# 2_matrix.net
KiCad netlist of a schematic drawn in Altium Designer
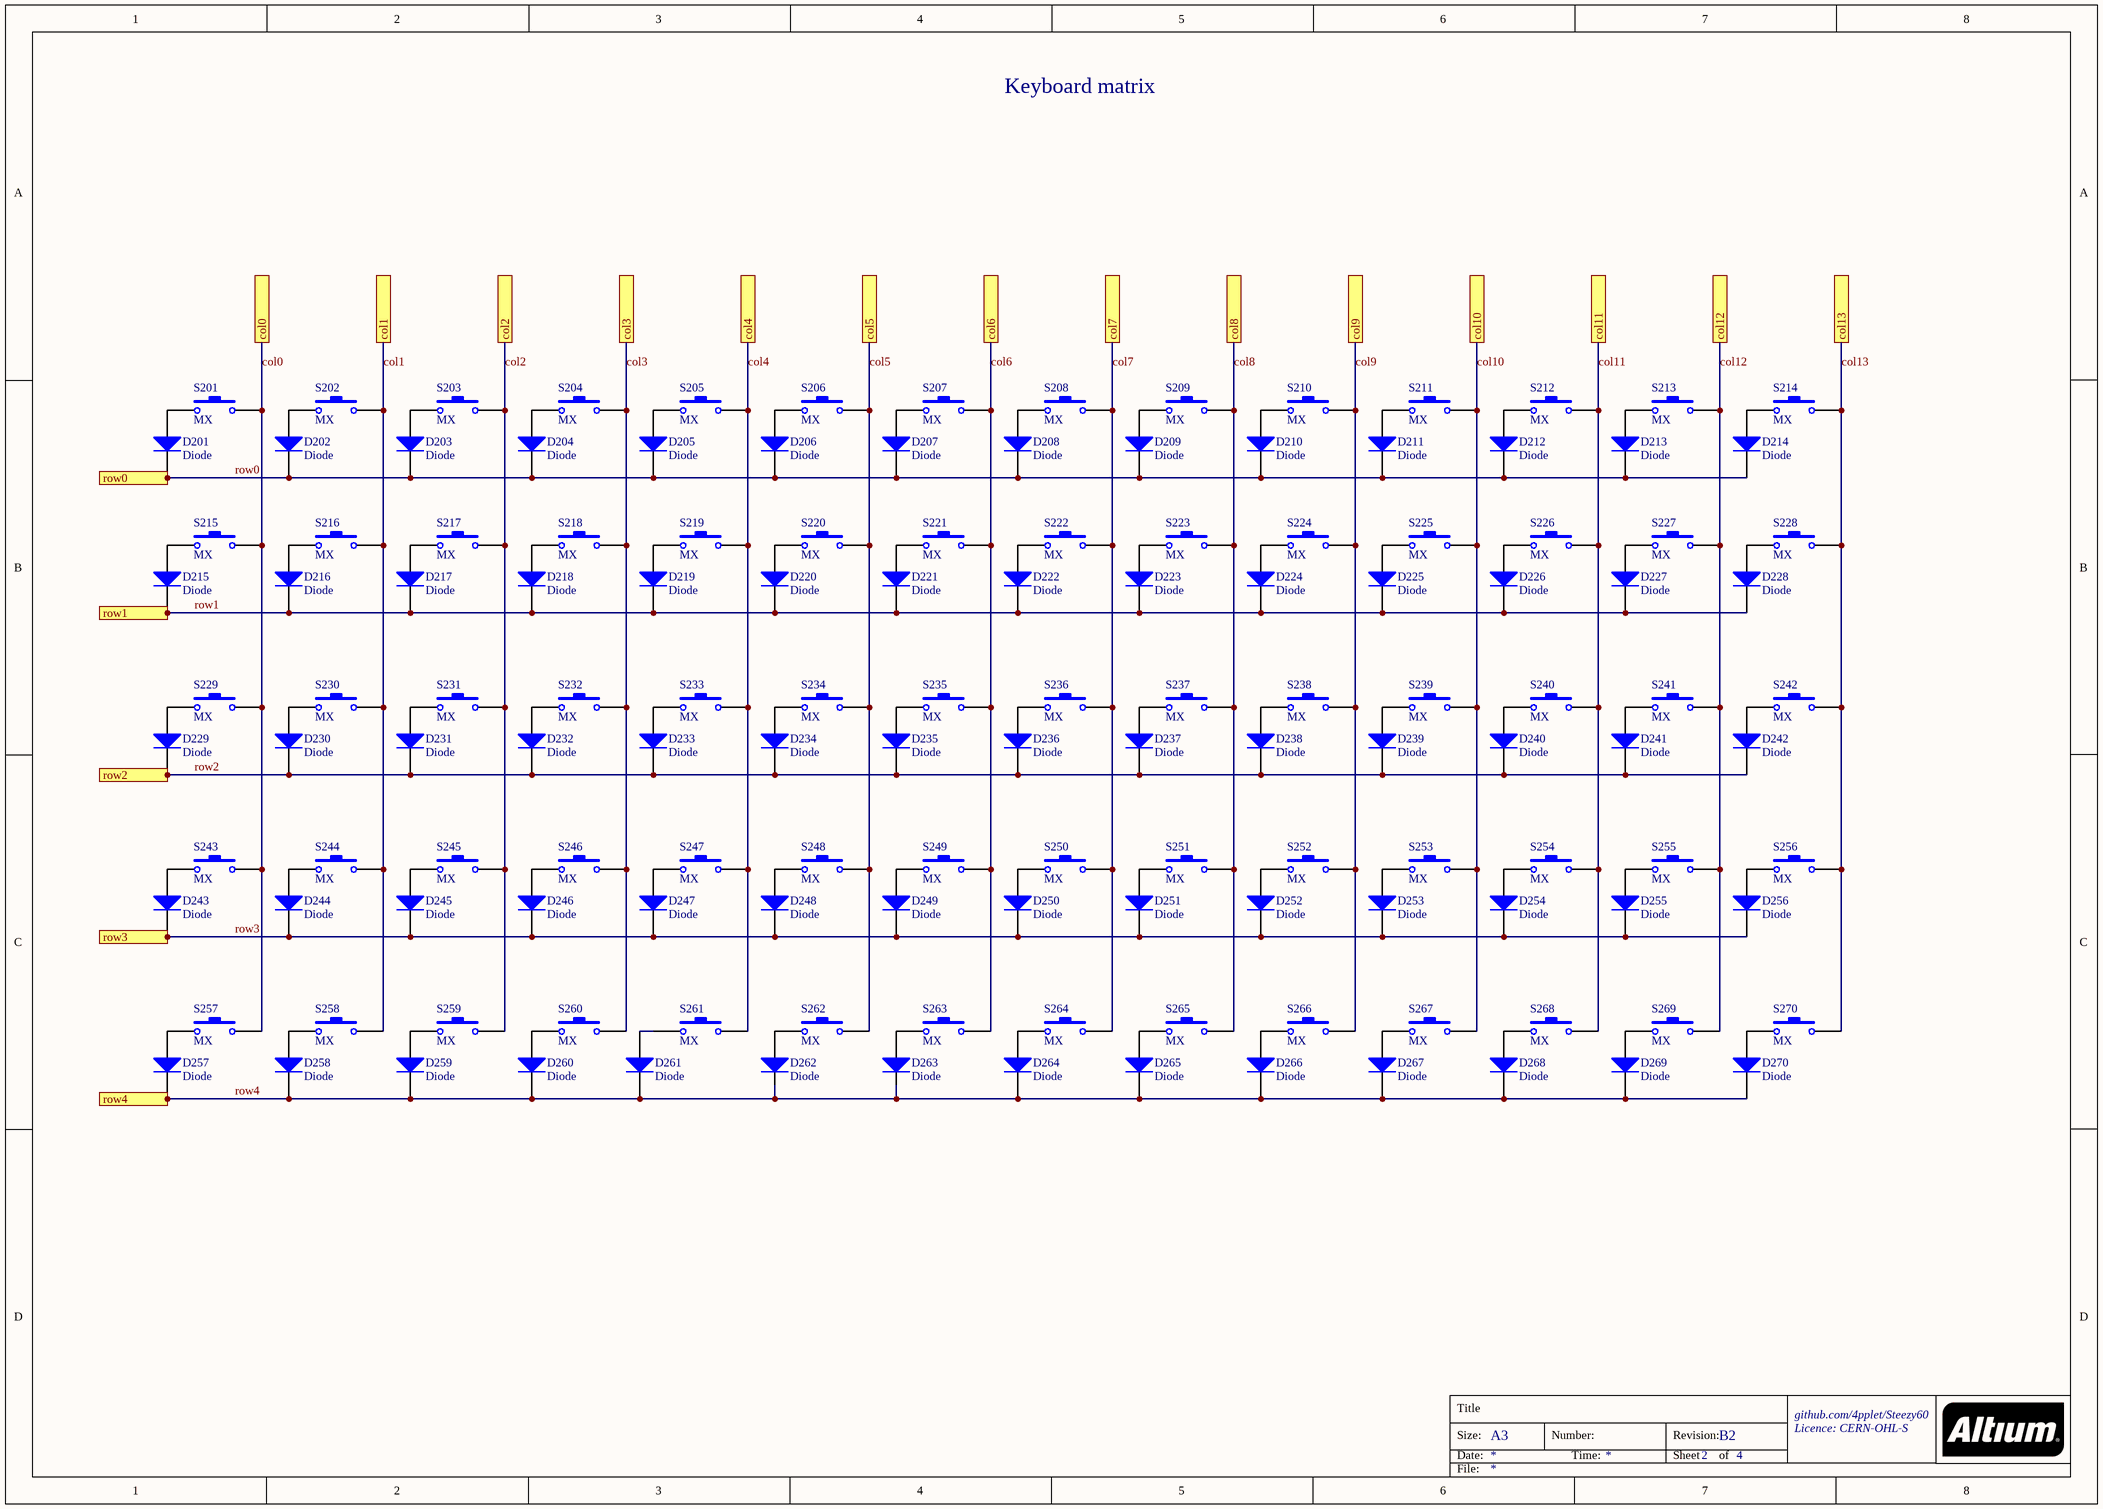
[diagram p0: 2_matrix.SchDoc]

(export (version "E")
  (design (tool "Eeschema 10.0.6"))
  (components
    (comp (ref "D201")
      (value "Diode")
      (footprint "SOD-123")
      (description "Default Diode")
      (fields (field (name "LCSC PART #") "C81598") (field (name "MRF.PART") "1N4148W"))
      (libsource (lib "Miscellaneous Devices") (part "Diode"))
    )
    (comp (ref "D202")
      (value "Diode")
      (footprint "SOD-123")
      (description "Default Diode")
      (fields (field (name "LCSC PART #") "C81598") (field (name "MRF.PART") "1N4148W"))
      (libsource (lib "Miscellaneous Devices") (part "Diode"))
    )
    (comp (ref "D203")
      (value "Diode")
      (footprint "SOD-123")
      (description "Default Diode")
      (fields (field (name "LCSC PART #") "C81598") (field (name "MRF.PART") "1N4148W"))
      (libsource (lib "Miscellaneous Devices") (part "Diode"))
    )
    (comp (ref "D204")
      (value "Diode")
      (footprint "SOD-123")
      (description "Default Diode")
      (fields (field (name "LCSC PART #") "C81598") (field (name "MRF.PART") "1N4148W"))
      (libsource (lib "Miscellaneous Devices") (part "Diode"))
    )
    (comp (ref "D205")
      (value "Diode")
      (footprint "SOD-123")
      (description "Default Diode")
      (fields (field (name "LCSC PART #") "C81598") (field (name "MRF.PART") "1N4148W"))
      (libsource (lib "Miscellaneous Devices") (part "Diode"))
    )
    (comp (ref "D206")
      (value "Diode")
      (footprint "SOD-123")
      (description "Default Diode")
      (fields (field (name "LCSC PART #") "C81598") (field (name "MRF.PART") "1N4148W"))
      (libsource (lib "Miscellaneous Devices") (part "Diode"))
    )
    (comp (ref "D207")
      (value "Diode")
      (footprint "SOD-123")
      (description "Default Diode")
      (fields (field (name "LCSC PART #") "C81598") (field (name "MRF.PART") "1N4148W"))
      (libsource (lib "Miscellaneous Devices") (part "Diode"))
    )
    (comp (ref "D208")
      (value "Diode")
      (footprint "SOD-123")
      (description "Default Diode")
      (fields (field (name "LCSC PART #") "C81598") (field (name "MRF.PART") "1N4148W"))
      (libsource (lib "Miscellaneous Devices") (part "Diode"))
    )
    (comp (ref "D209")
      (value "Diode")
      (footprint "SOD-123")
      (description "Default Diode")
      (fields (field (name "LCSC PART #") "C81598") (field (name "MRF.PART") "1N4148W"))
      (libsource (lib "Miscellaneous Devices") (part "Diode"))
    )
    (comp (ref "D210")
      (value "Diode")
      (footprint "SOD-123")
      (description "Default Diode")
      (fields (field (name "LCSC PART #") "C81598") (field (name "MRF.PART") "1N4148W"))
      (libsource (lib "Miscellaneous Devices") (part "Diode"))
    )
    (comp (ref "D211")
      (value "Diode")
      (footprint "SOD-123")
      (description "Default Diode")
      (fields (field (name "LCSC PART #") "C81598") (field (name "MRF.PART") "1N4148W"))
      (libsource (lib "Miscellaneous Devices") (part "Diode"))
    )
    (comp (ref "D212")
      (value "Diode")
      (footprint "SOD-123")
      (description "Default Diode")
      (fields (field (name "LCSC PART #") "C81598") (field (name "MRF.PART") "1N4148W"))
      (libsource (lib "Miscellaneous Devices") (part "Diode"))
    )
    (comp (ref "D213")
      (value "Diode")
      (footprint "SOD-123")
      (description "Default Diode")
      (fields (field (name "LCSC PART #") "C81598") (field (name "MRF.PART") "1N4148W"))
      (libsource (lib "Miscellaneous Devices") (part "Diode"))
    )
    (comp (ref "D214")
      (value "Diode")
      (footprint "SOD-123")
      (description "Default Diode")
      (fields (field (name "LCSC PART #") "C81598") (field (name "MRF.PART") "1N4148W"))
      (libsource (lib "Miscellaneous Devices") (part "Diode"))
    )
    (comp (ref "D215")
      (value "Diode")
      (footprint "SOD-123")
      (description "Default Diode")
      (fields (field (name "LCSC PART #") "C81598") (field (name "MRF.PART") "1N4148W"))
      (libsource (lib "Miscellaneous Devices") (part "Diode"))
    )
    (comp (ref "D216")
      (value "Diode")
      (footprint "SOD-123")
      (description "Default Diode")
      (fields (field (name "LCSC PART #") "C81598") (field (name "MRF.PART") "1N4148W"))
      (libsource (lib "Miscellaneous Devices") (part "Diode"))
    )
    (comp (ref "D217")
      (value "Diode")
      (footprint "SOD-123")
      (description "Default Diode")
      (fields (field (name "LCSC PART #") "C81598") (field (name "MRF.PART") "1N4148W"))
      (libsource (lib "Miscellaneous Devices") (part "Diode"))
    )
    (comp (ref "D218")
      (value "Diode")
      (footprint "SOD-123")
      (description "Default Diode")
      (fields (field (name "LCSC PART #") "C81598") (field (name "MRF.PART") "1N4148W"))
      (libsource (lib "Miscellaneous Devices") (part "Diode"))
    )
    (comp (ref "D219")
      (value "Diode")
      (footprint "SOD-123")
      (description "Default Diode")
      (fields (field (name "LCSC PART #") "C81598") (field (name "MRF.PART") "1N4148W"))
      (libsource (lib "Miscellaneous Devices") (part "Diode"))
    )
    (comp (ref "D220")
      (value "Diode")
      (footprint "SOD-123")
      (description "Default Diode")
      (fields (field (name "LCSC PART #") "C81598") (field (name "MRF.PART") "1N4148W"))
      (libsource (lib "Miscellaneous Devices") (part "Diode"))
    )
    (comp (ref "D221")
      (value "Diode")
      (footprint "SOD-123")
      (description "Default Diode")
      (fields (field (name "LCSC PART #") "C81598") (field (name "MRF.PART") "1N4148W"))
      (libsource (lib "Miscellaneous Devices") (part "Diode"))
    )
    (comp (ref "D222")
      (value "Diode")
      (footprint "SOD-123")
      (description "Default Diode")
      (fields (field (name "LCSC PART #") "C81598") (field (name "MRF.PART") "1N4148W"))
      (libsource (lib "Miscellaneous Devices") (part "Diode"))
    )
    (comp (ref "D223")
      (value "Diode")
      (footprint "SOD-123")
      (description "Default Diode")
      (fields (field (name "LCSC PART #") "C81598") (field (name "MRF.PART") "1N4148W"))
      (libsource (lib "Miscellaneous Devices") (part "Diode"))
    )
    (comp (ref "D224")
      (value "Diode")
      (footprint "SOD-123")
      (description "Default Diode")
      (fields (field (name "LCSC PART #") "C81598") (field (name "MRF.PART") "1N4148W"))
      (libsource (lib "Miscellaneous Devices") (part "Diode"))
    )
    (comp (ref "D225")
      (value "Diode")
      (footprint "SOD-123")
      (description "Default Diode")
      (fields (field (name "LCSC PART #") "C81598") (field (name "MRF.PART") "1N4148W"))
      (libsource (lib "Miscellaneous Devices") (part "Diode"))
    )
    (comp (ref "D226")
      (value "Diode")
      (footprint "SOD-123")
      (description "Default Diode")
      (fields (field (name "LCSC PART #") "C81598") (field (name "MRF.PART") "1N4148W"))
      (libsource (lib "Miscellaneous Devices") (part "Diode"))
    )
    (comp (ref "D227")
      (value "Diode")
      (footprint "SOD-123")
      (description "Default Diode")
      (fields (field (name "LCSC PART #") "C81598") (field (name "MRF.PART") "1N4148W"))
      (libsource (lib "Miscellaneous Devices") (part "Diode"))
    )
    (comp (ref "D228")
      (value "Diode")
      (footprint "SOD-123")
      (description "Default Diode")
      (fields (field (name "LCSC PART #") "C81598") (field (name "MRF.PART") "1N4148W"))
      (libsource (lib "Miscellaneous Devices") (part "Diode"))
    )
    (comp (ref "D229")
      (value "Diode")
      (footprint "SOD-123")
      (description "Default Diode")
      (fields (field (name "LCSC PART #") "C81598") (field (name "MRF.PART") "1N4148W"))
      (libsource (lib "Miscellaneous Devices") (part "Diode"))
    )
    (comp (ref "D230")
      (value "Diode")
      (footprint "SOD-123")
      (description "Default Diode")
      (fields (field (name "LCSC PART #") "C81598") (field (name "MRF.PART") "1N4148W"))
      (libsource (lib "Miscellaneous Devices") (part "Diode"))
    )
    (comp (ref "D231")
      (value "Diode")
      (footprint "SOD-123")
      (description "Default Diode")
      (fields (field (name "LCSC PART #") "C81598") (field (name "MRF.PART") "1N4148W"))
      (libsource (lib "Miscellaneous Devices") (part "Diode"))
    )
    (comp (ref "D232")
      (value "Diode")
      (footprint "SOD-123")
      (description "Default Diode")
      (fields (field (name "LCSC PART #") "C81598") (field (name "MRF.PART") "1N4148W"))
      (libsource (lib "Miscellaneous Devices") (part "Diode"))
    )
    (comp (ref "D233")
      (value "Diode")
      (footprint "SOD-123")
      (description "Default Diode")
      (fields (field (name "LCSC PART #") "C81598") (field (name "MRF.PART") "1N4148W"))
      (libsource (lib "Miscellaneous Devices") (part "Diode"))
    )
    (comp (ref "D234")
      (value "Diode")
      (footprint "SOD-123")
      (description "Default Diode")
      (fields (field (name "LCSC PART #") "C81598") (field (name "MRF.PART") "1N4148W"))
      (libsource (lib "Miscellaneous Devices") (part "Diode"))
    )
    (comp (ref "D235")
      (value "Diode")
      (footprint "SOD-123")
      (description "Default Diode")
      (fields (field (name "LCSC PART #") "C81598") (field (name "MRF.PART") "1N4148W"))
      (libsource (lib "Miscellaneous Devices") (part "Diode"))
    )
    (comp (ref "D236")
      (value "Diode")
      (footprint "SOD-123")
      (description "Default Diode")
      (fields (field (name "LCSC PART #") "C81598") (field (name "MRF.PART") "1N4148W"))
      (libsource (lib "Miscellaneous Devices") (part "Diode"))
    )
    (comp (ref "D237")
      (value "Diode")
      (footprint "SOD-123")
      (description "Default Diode")
      (fields (field (name "LCSC PART #") "C81598") (field (name "MRF.PART") "1N4148W"))
      (libsource (lib "Miscellaneous Devices") (part "Diode"))
    )
    (comp (ref "D238")
      (value "Diode")
      (footprint "SOD-123")
      (description "Default Diode")
      (fields (field (name "LCSC PART #") "C81598") (field (name "MRF.PART") "1N4148W"))
      (libsource (lib "Miscellaneous Devices") (part "Diode"))
    )
    (comp (ref "D239")
      (value "Diode")
      (footprint "SOD-123")
      (description "Default Diode")
      (fields (field (name "LCSC PART #") "C81598") (field (name "MRF.PART") "1N4148W"))
      (libsource (lib "Miscellaneous Devices") (part "Diode"))
    )
    (comp (ref "D240")
      (value "Diode")
      (footprint "SOD-123")
      (description "Default Diode")
      (fields (field (name "LCSC PART #") "C81598") (field (name "MRF.PART") "1N4148W"))
      (libsource (lib "Miscellaneous Devices") (part "Diode"))
    )
    (comp (ref "D241")
      (value "Diode")
      (footprint "SOD-123")
      (description "Default Diode")
      (fields (field (name "LCSC PART #") "C81598") (field (name "MRF.PART") "1N4148W"))
      (libsource (lib "Miscellaneous Devices") (part "Diode"))
    )
    (comp (ref "D242")
      (value "Diode")
      (footprint "SOD-123")
      (description "Default Diode")
      (fields (field (name "LCSC PART #") "C81598") (field (name "MRF.PART") "1N4148W"))
      (libsource (lib "Miscellaneous Devices") (part "Diode"))
    )
    (comp (ref "D243")
      (value "Diode")
      (footprint "SOD-123")
      (description "Default Diode")
      (fields (field (name "LCSC PART #") "C81598") (field (name "MRF.PART") "1N4148W"))
      (libsource (lib "Miscellaneous Devices") (part "Diode"))
    )
    (comp (ref "D244")
      (value "Diode")
      (footprint "SOD-123")
      (description "Default Diode")
      (fields (field (name "LCSC PART #") "C81598") (field (name "MRF.PART") "1N4148W"))
      (libsource (lib "Miscellaneous Devices") (part "Diode"))
    )
    (comp (ref "D245")
      (value "Diode")
      (footprint "SOD-123")
      (description "Default Diode")
      (fields (field (name "LCSC PART #") "C81598") (field (name "MRF.PART") "1N4148W"))
      (libsource (lib "Miscellaneous Devices") (part "Diode"))
    )
    (comp (ref "D246")
      (value "Diode")
      (footprint "SOD-123")
      (description "Default Diode")
      (fields (field (name "LCSC PART #") "C81598") (field (name "MRF.PART") "1N4148W"))
      (libsource (lib "Miscellaneous Devices") (part "Diode"))
    )
    (comp (ref "D247")
      (value "Diode")
      (footprint "SOD-123")
      (description "Default Diode")
      (fields (field (name "LCSC PART #") "C81598") (field (name "MRF.PART") "1N4148W"))
      (libsource (lib "Miscellaneous Devices") (part "Diode"))
    )
    (comp (ref "D248")
      (value "Diode")
      (footprint "SOD-123")
      (description "Default Diode")
      (fields (field (name "LCSC PART #") "C81598") (field (name "MRF.PART") "1N4148W"))
      (libsource (lib "Miscellaneous Devices") (part "Diode"))
    )
    (comp (ref "D249")
      (value "Diode")
      (footprint "SOD-123")
      (description "Default Diode")
      (fields (field (name "LCSC PART #") "C81598") (field (name "MRF.PART") "1N4148W"))
      (libsource (lib "Miscellaneous Devices") (part "Diode"))
    )
    (comp (ref "D250")
      (value "Diode")
      (footprint "SOD-123")
      (description "Default Diode")
      (fields (field (name "LCSC PART #") "C81598") (field (name "MRF.PART") "1N4148W"))
      (libsource (lib "Miscellaneous Devices") (part "Diode"))
    )
    (comp (ref "D251")
      (value "Diode")
      (footprint "SOD-123")
      (description "Default Diode")
      (fields (field (name "LCSC PART #") "C81598") (field (name "MRF.PART") "1N4148W"))
      (libsource (lib "Miscellaneous Devices") (part "Diode"))
    )
    (comp (ref "D252")
      (value "Diode")
      (footprint "SOD-123")
      (description "Default Diode")
      (fields (field (name "LCSC PART #") "C81598") (field (name "MRF.PART") "1N4148W"))
      (libsource (lib "Miscellaneous Devices") (part "Diode"))
    )
    (comp (ref "D253")
      (value "Diode")
      (footprint "SOD-123")
      (description "Default Diode")
      (fields (field (name "LCSC PART #") "C81598") (field (name "MRF.PART") "1N4148W"))
      (libsource (lib "Miscellaneous Devices") (part "Diode"))
    )
    (comp (ref "D254")
      (value "Diode")
      (footprint "SOD-123")
      (description "Default Diode")
      (fields (field (name "LCSC PART #") "C81598") (field (name "MRF.PART") "1N4148W"))
      (libsource (lib "Miscellaneous Devices") (part "Diode"))
    )
    (comp (ref "D255")
      (value "Diode")
      (footprint "SOD-123")
      (description "Default Diode")
      (fields (field (name "LCSC PART #") "C81598") (field (name "MRF.PART") "1N4148W"))
      (libsource (lib "Miscellaneous Devices") (part "Diode"))
    )
    (comp (ref "D256")
      (value "Diode")
      (footprint "SOD-123")
      (description "Default Diode")
      (fields (field (name "LCSC PART #") "C81598") (field (name "MRF.PART") "1N4148W"))
      (libsource (lib "Miscellaneous Devices") (part "Diode"))
    )
    (comp (ref "D257")
      (value "Diode")
      (footprint "SOD-123")
      (description "Default Diode")
      (fields (field (name "LCSC PART #") "C81598") (field (name "MRF.PART") "1N4148W"))
      (libsource (lib "Miscellaneous Devices") (part "Diode"))
    )
    (comp (ref "D258")
      (value "Diode")
      (footprint "SOD-123")
      (description "Default Diode")
      (fields (field (name "LCSC PART #") "C81598") (field (name "MRF.PART") "1N4148W"))
      (libsource (lib "Miscellaneous Devices") (part "Diode"))
    )
    (comp (ref "D259")
      (value "Diode")
      (footprint "SOD-123")
      (description "Default Diode")
      (fields (field (name "LCSC PART #") "C81598") (field (name "MRF.PART") "1N4148W"))
      (libsource (lib "Miscellaneous Devices") (part "Diode"))
    )
    (comp (ref "D260")
      (value "Diode")
      (footprint "SOD-123")
      (description "Default Diode")
      (fields (field (name "LCSC PART #") "C81598") (field (name "MRF.PART") "1N4148W"))
      (libsource (lib "Miscellaneous Devices") (part "Diode"))
    )
    (comp (ref "D261")
      (value "Diode")
      (footprint "SOD-123")
      (description "Default Diode")
      (fields (field (name "LCSC PART #") "C81598") (field (name "MRF.PART") "1N4148W"))
      (libsource (lib "Miscellaneous Devices") (part "Diode"))
    )
    (comp (ref "D262")
      (value "Diode")
      (footprint "SOD-123")
      (description "Default Diode")
      (fields (field (name "LCSC PART #") "C81598") (field (name "MRF.PART") "1N4148W"))
      (libsource (lib "Miscellaneous Devices") (part "Diode"))
    )
    (comp (ref "D263")
      (value "Diode")
      (footprint "SOD-123")
      (description "Default Diode")
      (fields (field (name "LCSC PART #") "C81598") (field (name "MRF.PART") "1N4148W"))
      (libsource (lib "Miscellaneous Devices") (part "Diode"))
    )
    (comp (ref "D264")
      (value "Diode")
      (footprint "SOD-123")
      (description "Default Diode")
      (fields (field (name "LCSC PART #") "C81598") (field (name "MRF.PART") "1N4148W"))
      (libsource (lib "Miscellaneous Devices") (part "Diode"))
    )
    (comp (ref "D265")
      (value "Diode")
      (footprint "SOD-123")
      (description "Default Diode")
      (fields (field (name "LCSC PART #") "C81598") (field (name "MRF.PART") "1N4148W"))
      (libsource (lib "Miscellaneous Devices") (part "Diode"))
    )
    (comp (ref "D266")
      (value "Diode")
      (footprint "SOD-123")
      (description "Default Diode")
      (fields (field (name "LCSC PART #") "C81598") (field (name "MRF.PART") "1N4148W"))
      (libsource (lib "Miscellaneous Devices") (part "Diode"))
    )
    (comp (ref "D267")
      (value "Diode")
      (footprint "SOD-123")
      (description "Default Diode")
      (fields (field (name "LCSC PART #") "C81598") (field (name "MRF.PART") "1N4148W"))
      (libsource (lib "Miscellaneous Devices") (part "Diode"))
    )
    (comp (ref "D268")
      (value "Diode")
      (footprint "SOD-123")
      (description "Default Diode")
      (fields (field (name "LCSC PART #") "C81598") (field (name "MRF.PART") "1N4148W"))
      (libsource (lib "Miscellaneous Devices") (part "Diode"))
    )
    (comp (ref "D269")
      (value "Diode")
      (footprint "SOD-123")
      (description "Default Diode")
      (fields (field (name "LCSC PART #") "C81598") (field (name "MRF.PART") "1N4148W"))
      (libsource (lib "Miscellaneous Devices") (part "Diode"))
    )
    (comp (ref "D270")
      (value "Diode")
      (footprint "SOD-123")
      (description "Default Diode")
      (fields (field (name "LCSC PART #") "C81598") (field (name "MRF.PART") "1N4148W"))
      (libsource (lib "Miscellaneous Devices") (part "Diode"))
    )
    (comp (ref "S201")
      (value "MX")
      (footprint "SMK-switch - switched polarity")
      (description "Switch")
      (libsource (lib "Miscellaneous Devices") (part "SW-PB"))
    )
    (comp (ref "S202")
      (value "MX")
      (footprint "SMK-switch - switched polarity")
      (description "Switch")
      (libsource (lib "Miscellaneous Devices") (part "SW-PB"))
    )
    (comp (ref "S203")
      (value "MX")
      (footprint "SMK-switch - switched polarity")
      (description "Switch")
      (libsource (lib "Miscellaneous Devices") (part "SW-PB"))
    )
    (comp (ref "S204")
      (value "MX")
      (footprint "SMK-switch - switched polarity")
      (description "Switch")
      (libsource (lib "Miscellaneous Devices") (part "SW-PB"))
    )
    (comp (ref "S205")
      (value "MX")
      (footprint "SMK-switch - switched polarity")
      (description "Switch")
      (libsource (lib "Miscellaneous Devices") (part "SW-PB"))
    )
    (comp (ref "S206")
      (value "MX")
      (footprint "SMK-switch - switched polarity")
      (description "Switch")
      (libsource (lib "Miscellaneous Devices") (part "SW-PB"))
    )
    (comp (ref "S207")
      (value "MX")
      (footprint "SMK-switch - switched polarity")
      (description "Switch")
      (libsource (lib "Miscellaneous Devices") (part "SW-PB"))
    )
    (comp (ref "S208")
      (value "MX")
      (footprint "SMK-switch - switched polarity")
      (description "Switch")
      (libsource (lib "Miscellaneous Devices") (part "SW-PB"))
    )
    (comp (ref "S209")
      (value "MX")
      (footprint "SMK-switch")
      (description "Switch")
      (libsource (lib "Miscellaneous Devices") (part "SW-PB"))
    )
    (comp (ref "S210")
      (value "MX")
      (footprint "SMK-switch")
      (description "Switch")
      (libsource (lib "Miscellaneous Devices") (part "SW-PB"))
    )
    (comp (ref "S211")
      (value "MX")
      (footprint "SMK-switch")
      (description "Switch")
      (libsource (lib "Miscellaneous Devices") (part "SW-PB"))
    )
    (comp (ref "S212")
      (value "MX")
      (footprint "SMK-switch")
      (description "Switch")
      (libsource (lib "Miscellaneous Devices") (part "SW-PB"))
    )
    (comp (ref "S213")
      (value "MX")
      (footprint "SMK-switch")
      (description "Switch")
      (libsource (lib "Miscellaneous Devices") (part "SW-PB"))
    )
    (comp (ref "S214")
      (value "MX")
      (footprint "SMK-switch")
      (description "Switch")
      (libsource (lib "Miscellaneous Devices") (part "SW-PB"))
    )
    (comp (ref "S215")
      (value "MX")
      (footprint "SMK-switch - 1.5U")
      (description "TAB")
      (libsource (lib "Miscellaneous Devices") (part "SW-PB"))
    )
    (comp (ref "S216")
      (value "MX")
      (footprint "SMK-switch")
      (description "Switch")
      (libsource (lib "Miscellaneous Devices") (part "SW-PB"))
    )
    (comp (ref "S217")
      (value "MX")
      (footprint "SMK-switch - switched polarity")
      (description "Switch")
      (libsource (lib "Miscellaneous Devices") (part "SW-PB"))
    )
    (comp (ref "S218")
      (value "MX")
      (footprint "SMK-switch - switched polarity")
      (description "Switch")
      (libsource (lib "Miscellaneous Devices") (part "SW-PB"))
    )
    (comp (ref "S219")
      (value "MX")
      (footprint "SMK-switch - switched polarity")
      (description "Switch")
      (libsource (lib "Miscellaneous Devices") (part "SW-PB"))
    )
    (comp (ref "S220")
      (value "MX")
      (footprint "SMK-switch - switched polarity")
      (description "Switch")
      (libsource (lib "Miscellaneous Devices") (part "SW-PB"))
    )
    (comp (ref "S221")
      (value "MX")
      (footprint "SMK-switch - switched polarity")
      (description "Switch")
      (libsource (lib "Miscellaneous Devices") (part "SW-PB"))
    )
    (comp (ref "S222")
      (value "MX")
      (footprint "SMK-switch - switched polarity")
      (description "Switch")
      (libsource (lib "Miscellaneous Devices") (part "SW-PB"))
    )
    (comp (ref "S223")
      (value "MX")
      (footprint "SMK-switch - switched polarity")
      (description "Switch")
      (libsource (lib "Miscellaneous Devices") (part "SW-PB"))
    )
    (comp (ref "S224")
      (value "MX")
      (footprint "SMK-switch - switched polarity")
      (description "Switch")
      (libsource (lib "Miscellaneous Devices") (part "SW-PB"))
    )
    (comp (ref "S225")
      (value "MX")
      (footprint "SMK-switch")
      (description "Switch")
      (libsource (lib "Miscellaneous Devices") (part "SW-PB"))
    )
    (comp (ref "S226")
      (value "MX")
      (footprint "SMK-switch")
      (description "Switch")
      (libsource (lib "Miscellaneous Devices") (part "SW-PB"))
    )
    (comp (ref "S227")
      (value "MX")
      (footprint "SMK-switch - offset-R")
      (description "Switch")
      (libsource (lib "Miscellaneous Devices") (part "SW-PB"))
    )
    (comp (ref "S228")
      (value "MX")
      (footprint "SMK-switch - 1.5U")
      (description "Switch")
      (libsource (lib "Miscellaneous Devices") (part "SW-PB"))
    )
    (comp (ref "S229")
      (value "MX")
      (footprint "SMK-SWITCH - CAPS - V2")
      (description "Switch")
      (libsource (lib "Miscellaneous Devices") (part "SW-PB"))
    )
    (comp (ref "S230")
      (value "MX")
      (footprint "SMK-switch")
      (description "Switch")
      (libsource (lib "Miscellaneous Devices") (part "SW-PB"))
    )
    (comp (ref "S231")
      (value "MX")
      (footprint "SMK-switch - switched polarity")
      (description "Switch")
      (libsource (lib "Miscellaneous Devices") (part "SW-PB"))
    )
    (comp (ref "S232")
      (value "MX")
      (footprint "SMK-switch - switched polarity")
      (description "Switch")
      (libsource (lib "Miscellaneous Devices") (part "SW-PB"))
    )
    (comp (ref "S233")
      (value "MX")
      (footprint "SMK-switch")
      (description "Switch")
      (libsource (lib "Miscellaneous Devices") (part "SW-PB"))
    )
    (comp (ref "S234")
      (value "MX")
      (footprint "SMK-switch - switched polarity")
      (description "Switch")
      (libsource (lib "Miscellaneous Devices") (part "SW-PB"))
    )
    (comp (ref "S235")
      (value "MX")
      (footprint "SMK-switch - switched polarity")
      (description "Switch")
      (libsource (lib "Miscellaneous Devices") (part "SW-PB"))
    )
    (comp (ref "S236")
      (value "MX")
      (footprint "SMK-switch - switched polarity")
      (description "Switch")
      (libsource (lib "Miscellaneous Devices") (part "SW-PB"))
    )
    (comp (ref "S237")
      (value "MX")
      (footprint "SMK-switch - switched polarity")
      (description "Switch")
      (libsource (lib "Miscellaneous Devices") (part "SW-PB"))
    )
    (comp (ref "S238")
      (value "MX")
      (footprint "SMK-switch - switched polarity")
      (description "Switch")
      (libsource (lib "Miscellaneous Devices") (part "SW-PB"))
    )
    (comp (ref "S239")
      (value "MX")
      (footprint "SMK-switch")
      (description "Switch")
      (libsource (lib "Miscellaneous Devices") (part "SW-PB"))
    )
    (comp (ref "S240")
      (value "MX")
      (footprint "SMK-switch")
      (description "Switch")
      (libsource (lib "Miscellaneous Devices") (part "SW-PB"))
    )
    (comp (ref "S241")
      (value "MX")
      (footprint "SMK-switch")
      (description "Switch")
      (libsource (lib "Miscellaneous Devices") (part "SW-PB"))
    )
    (comp (ref "S242")
      (value "MX")
      (footprint "SMK-switch - Enter - rotated stab")
      (description "Switch")
      (libsource (lib "Miscellaneous Devices") (part "SW-PB"))
    )
    (comp (ref "S243")
      (value "MX")
      (footprint "SMK-switch - Left shift")
      (description "Switch")
      (libsource (lib "Miscellaneous Devices") (part "SW-PB"))
    )
    (comp (ref "S244")
      (value "MX")
      (footprint "SMK-switch - smalleroffset-R")
      (description "Switch")
      (libsource (lib "Miscellaneous Devices") (part "SW-PB"))
    )
    (comp (ref "S245")
      (value "MX")
      (footprint "SMK-switch - offset")
      (description "Switch")
      (libsource (lib "Miscellaneous Devices") (part "SW-PB"))
    )
    (comp (ref "S246")
      (value "MX")
      (footprint "SMK-switch - offset")
      (description "Switch")
      (libsource (lib "Miscellaneous Devices") (part "SW-PB"))
    )
    (comp (ref "S247")
      (value "MX")
      (footprint "SMK-switch - offset")
      (description "Switch")
      (libsource (lib "Miscellaneous Devices") (part "SW-PB"))
    )
    (comp (ref "S248")
      (value "MX")
      (footprint "SMK-switch - offset")
      (description "Switch")
      (libsource (lib "Miscellaneous Devices") (part "SW-PB"))
    )
    (comp (ref "S249")
      (value "MX")
      (footprint "SMK-switch - offset")
      (description "Switch")
      (libsource (lib "Miscellaneous Devices") (part "SW-PB"))
    )
    (comp (ref "S250")
      (value "MX")
      (footprint "SMK-switch - offset")
      (description "Switch")
      (libsource (lib "Miscellaneous Devices") (part "SW-PB"))
    )
    (comp (ref "S251")
      (value "MX")
      (footprint "SMK-switch - offset")
      (description "Switch")
      (libsource (lib "Miscellaneous Devices") (part "SW-PB"))
    )
    (comp (ref "S252")
      (value "MX")
      (footprint "SMK-switch - offset")
      (description "Switch")
      (libsource (lib "Miscellaneous Devices") (part "SW-PB"))
    )
    (comp (ref "S253")
      (value "MX")
      (footprint "SMK-switch - offset")
      (description "Switch")
      (libsource (lib "Miscellaneous Devices") (part "SW-PB"))
    )
    (comp (ref "S254")
      (value "MX")
      (footprint "SMK-switch - offset")
      (description "Switch")
      (libsource (lib "Miscellaneous Devices") (part "SW-PB"))
    )
    (comp (ref "S255")
      (value "MX")
      (footprint "SMK-switch - CRAZY SHIFT")
      (description "Switch")
      (libsource (lib "Miscellaneous Devices") (part "SW-PB"))
    )
    (comp (ref "S256")
      (value "MX")
      (footprint "SMK-switch - right shift")
      (description "Switch")
      (libsource (lib "Miscellaneous Devices") (part "SW-PB"))
    )
    (comp (ref "S257")
      (value "MX")
      (footprint "SMK-switch - L_CTRL")
      (description "Switch")
      (libsource (lib "Miscellaneous Devices") (part "SW-PB"))
    )
    (comp (ref "S258")
      (value "MX")
      (footprint "SMK-switch - L_WIN")
      (description "Switch")
      (libsource (lib "Miscellaneous Devices") (part "SW-PB"))
    )
    (comp (ref "S259")
      (value "MX")
      (footprint "SMK-switch")
      (description "Switch")
      (libsource (lib "Miscellaneous Devices") (part "SW-PB"))
    )
    (comp (ref "S260")
      (value "MX")
      (footprint "SMK-switch - L_alt")
      (description "Switch")
      (libsource (lib "Miscellaneous Devices") (part "SW-PB"))
    )
    (comp (ref "S261")
      (value "MX")
      (footprint "SMK-switch - L split space")
      (description "Switch")
      (libsource (lib "Miscellaneous Devices") (part "SW-PB"))
    )
    (comp (ref "S262")
      (value "MX")
      (footprint "SMK-switch - Space")
      (description "Switch")
      (libsource (lib "Miscellaneous Devices") (part "SW-PB"))
    )
    (comp (ref "S263")
      (value "MX")
      (footprint "SMK-switch - R split space")
      (description "Switch")
      (libsource (lib "Miscellaneous Devices") (part "SW-PB"))
    )
    (comp (ref "S264")
      (value "MX")
      (footprint "SMK-switch - R PN")
      (description "Switch")
      (libsource (lib "Miscellaneous Devices") (part "SW-PB"))
    )
    (comp (ref "S265")
      (value "MX")
      (footprint "SMK-switch - R_alt")
      (description "Switch")
      (libsource (lib "Miscellaneous Devices") (part "SW-PB"))
    )
    (comp (ref "S266")
      (value "MX")
      (footprint "SMK-switch")
      (description "Switch")
      (libsource (lib "Miscellaneous Devices") (part "SW-PB"))
    )
    (comp (ref "S267")
      (value "MX")
      (footprint "SMK-switch - R_WIN")
      (description "Switch")
      (libsource (lib "Miscellaneous Devices") (part "SW-PB"))
    )
    (comp (ref "S268")
      (value "MX")
      (footprint "SMK-switch - R_CTRL")
      (description "Switch")
      (libsource (lib "Miscellaneous Devices") (part "SW-PB"))
    )
    (comp (ref "S269")
      (value "MX")
      (footprint "SMK-switch - fn and shift")
      (description "Switch")
      (libsource (lib "Miscellaneous Devices") (part "SW-PB"))
    )
    (comp (ref "S270")
      (value "MX")
      (footprint "SMK-switch - backspace")
      (description "Switch")
      (libsource (lib "Miscellaneous Devices") (part "SW-PB"))
    )
  )
  (nets
    (net (code "1") (name "/col0") (class "Default")
      (node (ref "S201") (pin "2") (pinfunction "2_2") (pintype "passive"))
      (node (ref "S215") (pin "1") (pinfunction "1_1") (pintype "passive"))
      (node (ref "S229") (pin "2") (pinfunction "2_2") (pintype "passive"))
      (node (ref "S243") (pin "2") (pinfunction "2_2") (pintype "passive"))
      (node (ref "S257") (pin "2") (pinfunction "2_2") (pintype "passive"))
    )
    (net (code "2") (name "/col1") (class "Default")
      (node (ref "S202") (pin "2") (pinfunction "2_2") (pintype "passive"))
      (node (ref "S216") (pin "2") (pinfunction "2_2") (pintype "passive"))
      (node (ref "S230") (pin "2") (pinfunction "2_2") (pintype "passive"))
      (node (ref "S244") (pin "2") (pinfunction "2_2") (pintype "passive"))
      (node (ref "S258") (pin "2") (pinfunction "2_2") (pintype "passive"))
    )
    (net (code "3") (name "/col2") (class "Default")
      (node (ref "S203") (pin "2") (pinfunction "2_2") (pintype "passive"))
      (node (ref "S217") (pin "2") (pinfunction "2_2") (pintype "passive"))
      (node (ref "S231") (pin "2") (pinfunction "2_2") (pintype "passive"))
      (node (ref "S245") (pin "2") (pinfunction "2_2") (pintype "passive"))
      (node (ref "S259") (pin "2") (pinfunction "2_2") (pintype "passive"))
    )
    (net (code "4") (name "/col3") (class "Default")
      (node (ref "S204") (pin "2") (pinfunction "2_2") (pintype "passive"))
      (node (ref "S218") (pin "2") (pinfunction "2_2") (pintype "passive"))
      (node (ref "S232") (pin "2") (pinfunction "2_2") (pintype "passive"))
      (node (ref "S246") (pin "2") (pinfunction "2_2") (pintype "passive"))
      (node (ref "S260") (pin "2") (pinfunction "2_2") (pintype "passive"))
    )
    (net (code "5") (name "/col4") (class "Default")
      (node (ref "S205") (pin "2") (pinfunction "2_2") (pintype "passive"))
      (node (ref "S219") (pin "2") (pinfunction "2_2") (pintype "passive"))
      (node (ref "S233") (pin "2") (pinfunction "2_2") (pintype "passive"))
      (node (ref "S247") (pin "2") (pinfunction "2_2") (pintype "passive"))
      (node (ref "S261") (pin "2") (pinfunction "2_2") (pintype "passive"))
    )
    (net (code "6") (name "/col5") (class "Default")
      (node (ref "S206") (pin "2") (pinfunction "2_2") (pintype "passive"))
      (node (ref "S220") (pin "2") (pinfunction "2_2") (pintype "passive"))
      (node (ref "S234") (pin "2") (pinfunction "2_2") (pintype "passive"))
      (node (ref "S248") (pin "2") (pinfunction "2_2") (pintype "passive"))
      (node (ref "S262") (pin "2") (pinfunction "2_2") (pintype "passive"))
    )
    (net (code "7") (name "/col6") (class "Default")
      (node (ref "S207") (pin "2") (pinfunction "2_2") (pintype "passive"))
      (node (ref "S221") (pin "2") (pinfunction "2_2") (pintype "passive"))
      (node (ref "S235") (pin "2") (pinfunction "2_2") (pintype "passive"))
      (node (ref "S249") (pin "2") (pinfunction "2_2") (pintype "passive"))
      (node (ref "S263") (pin "2") (pinfunction "2_2") (pintype "passive"))
    )
    (net (code "8") (name "/col7") (class "Default")
      (node (ref "S208") (pin "2") (pinfunction "2_2") (pintype "passive"))
      (node (ref "S222") (pin "2") (pinfunction "2_2") (pintype "passive"))
      (node (ref "S236") (pin "2") (pinfunction "2_2") (pintype "passive"))
      (node (ref "S250") (pin "2") (pinfunction "2_2") (pintype "passive"))
      (node (ref "S264") (pin "2") (pinfunction "2_2") (pintype "passive"))
    )
    (net (code "9") (name "/col8") (class "Default")
      (node (ref "S209") (pin "2") (pinfunction "2_2") (pintype "passive"))
      (node (ref "S223") (pin "2") (pinfunction "2_2") (pintype "passive"))
      (node (ref "S237") (pin "2") (pinfunction "2_2") (pintype "passive"))
      (node (ref "S251") (pin "2") (pinfunction "2_2") (pintype "passive"))
      (node (ref "S265") (pin "2") (pinfunction "2_2") (pintype "passive"))
    )
    (net (code "10") (name "/col9") (class "Default")
      (node (ref "S210") (pin "2") (pinfunction "2_2") (pintype "passive"))
      (node (ref "S224") (pin "2") (pinfunction "2_2") (pintype "passive"))
      (node (ref "S238") (pin "2") (pinfunction "2_2") (pintype "passive"))
      (node (ref "S252") (pin "2") (pinfunction "2_2") (pintype "passive"))
      (node (ref "S266") (pin "2") (pinfunction "2_2") (pintype "passive"))
    )
    (net (code "11") (name "/col10") (class "Default")
      (node (ref "S211") (pin "2") (pinfunction "2_2") (pintype "passive"))
      (node (ref "S225") (pin "2") (pinfunction "2_2") (pintype "passive"))
      (node (ref "S239") (pin "2") (pinfunction "2_2") (pintype "passive"))
      (node (ref "S253") (pin "2") (pinfunction "2_2") (pintype "passive"))
      (node (ref "S267") (pin "2") (pinfunction "2_2") (pintype "passive"))
    )
    (net (code "12") (name "/col11") (class "Default")
      (node (ref "S212") (pin "2") (pinfunction "2_2") (pintype "passive"))
      (node (ref "S226") (pin "2") (pinfunction "2_2") (pintype "passive"))
      (node (ref "S240") (pin "2") (pinfunction "2_2") (pintype "passive"))
      (node (ref "S254") (pin "2") (pinfunction "2_2") (pintype "passive"))
      (node (ref "S268") (pin "2") (pinfunction "2_2") (pintype "passive"))
    )
    (net (code "13") (name "/col12") (class "Default")
      (node (ref "S213") (pin "2") (pinfunction "2_2") (pintype "passive"))
      (node (ref "S227") (pin "2") (pinfunction "2_2") (pintype "passive"))
      (node (ref "S241") (pin "2") (pinfunction "2_2") (pintype "passive"))
      (node (ref "S255") (pin "2") (pinfunction "2_2") (pintype "passive"))
      (node (ref "S269") (pin "2") (pinfunction "2_2") (pintype "passive"))
    )
    (net (code "14") (name "/col13") (class "Default")
      (node (ref "S214") (pin "2") (pinfunction "2_2") (pintype "passive"))
      (node (ref "S228") (pin "2") (pinfunction "2_2") (pintype "passive"))
      (node (ref "S242") (pin "2") (pinfunction "2_2") (pintype "passive"))
      (node (ref "S256") (pin "2") (pinfunction "2_2") (pintype "passive"))
      (node (ref "S270") (pin "2") (pinfunction "2_2") (pintype "passive"))
    )
    (net (code "15") (name "/row0") (class "Default")
      (node (ref "D201") (pin "2") (pinfunction "K_2") (pintype "passive"))
      (node (ref "D202") (pin "2") (pinfunction "K_2") (pintype "passive"))
      (node (ref "D203") (pin "2") (pinfunction "K_2") (pintype "passive"))
      (node (ref "D204") (pin "2") (pinfunction "K_2") (pintype "passive"))
      (node (ref "D205") (pin "2") (pinfunction "K_2") (pintype "passive"))
      (node (ref "D206") (pin "2") (pinfunction "K_2") (pintype "passive"))
      (node (ref "D207") (pin "2") (pinfunction "K_2") (pintype "passive"))
      (node (ref "D208") (pin "2") (pinfunction "K_2") (pintype "passive"))
      (node (ref "D209") (pin "2") (pinfunction "K_2") (pintype "passive"))
      (node (ref "D210") (pin "2") (pinfunction "K_2") (pintype "passive"))
      (node (ref "D211") (pin "2") (pinfunction "K_2") (pintype "passive"))
      (node (ref "D212") (pin "2") (pinfunction "K_2") (pintype "passive"))
      (node (ref "D213") (pin "2") (pinfunction "K_2") (pintype "passive"))
      (node (ref "D214") (pin "2") (pinfunction "K_2") (pintype "passive"))
    )
    (net (code "16") (name "/row1") (class "Default")
      (node (ref "D215") (pin "2") (pinfunction "K_2") (pintype "passive"))
      (node (ref "D216") (pin "2") (pinfunction "K_2") (pintype "passive"))
      (node (ref "D217") (pin "2") (pinfunction "K_2") (pintype "passive"))
      (node (ref "D218") (pin "2") (pinfunction "K_2") (pintype "passive"))
      (node (ref "D219") (pin "2") (pinfunction "K_2") (pintype "passive"))
      (node (ref "D220") (pin "2") (pinfunction "K_2") (pintype "passive"))
      (node (ref "D221") (pin "2") (pinfunction "K_2") (pintype "passive"))
      (node (ref "D222") (pin "2") (pinfunction "K_2") (pintype "passive"))
      (node (ref "D223") (pin "2") (pinfunction "K_2") (pintype "passive"))
      (node (ref "D224") (pin "2") (pinfunction "K_2") (pintype "passive"))
      (node (ref "D225") (pin "2") (pinfunction "K_2") (pintype "passive"))
      (node (ref "D226") (pin "2") (pinfunction "K_2") (pintype "passive"))
      (node (ref "D227") (pin "2") (pinfunction "K_2") (pintype "passive"))
      (node (ref "D228") (pin "2") (pinfunction "K_2") (pintype "passive"))
    )
    (net (code "17") (name "/row2") (class "Default")
      (node (ref "D229") (pin "2") (pinfunction "K_2") (pintype "passive"))
      (node (ref "D230") (pin "2") (pinfunction "K_2") (pintype "passive"))
      (node (ref "D231") (pin "2") (pinfunction "K_2") (pintype "passive"))
      (node (ref "D232") (pin "2") (pinfunction "K_2") (pintype "passive"))
      (node (ref "D233") (pin "2") (pinfunction "K_2") (pintype "passive"))
      (node (ref "D234") (pin "2") (pinfunction "K_2") (pintype "passive"))
      (node (ref "D235") (pin "2") (pinfunction "K_2") (pintype "passive"))
      (node (ref "D236") (pin "2") (pinfunction "K_2") (pintype "passive"))
      (node (ref "D237") (pin "2") (pinfunction "K_2") (pintype "passive"))
      (node (ref "D238") (pin "2") (pinfunction "K_2") (pintype "passive"))
      (node (ref "D239") (pin "2") (pinfunction "K_2") (pintype "passive"))
      (node (ref "D240") (pin "2") (pinfunction "K_2") (pintype "passive"))
      (node (ref "D241") (pin "2") (pinfunction "K_2") (pintype "passive"))
      (node (ref "D242") (pin "2") (pinfunction "K_2") (pintype "passive"))
    )
    (net (code "18") (name "/row3") (class "Default")
      (node (ref "D243") (pin "2") (pinfunction "K_2") (pintype "passive"))
      (node (ref "D244") (pin "2") (pinfunction "K_2") (pintype "passive"))
      (node (ref "D245") (pin "2") (pinfunction "K_2") (pintype "passive"))
      (node (ref "D246") (pin "2") (pinfunction "K_2") (pintype "passive"))
      (node (ref "D247") (pin "2") (pinfunction "K_2") (pintype "passive"))
      (node (ref "D248") (pin "2") (pinfunction "K_2") (pintype "passive"))
      (node (ref "D249") (pin "2") (pinfunction "K_2") (pintype "passive"))
      (node (ref "D250") (pin "2") (pinfunction "K_2") (pintype "passive"))
      (node (ref "D251") (pin "2") (pinfunction "K_2") (pintype "passive"))
      (node (ref "D252") (pin "2") (pinfunction "K_2") (pintype "passive"))
      (node (ref "D253") (pin "2") (pinfunction "K_2") (pintype "passive"))
      (node (ref "D254") (pin "2") (pinfunction "K_2") (pintype "passive"))
      (node (ref "D255") (pin "2") (pinfunction "K_2") (pintype "passive"))
      (node (ref "D256") (pin "2") (pinfunction "K_2") (pintype "passive"))
    )
    (net (code "19") (name "/row4") (class "Default")
      (node (ref "D257") (pin "2") (pinfunction "K_2") (pintype "passive"))
      (node (ref "D258") (pin "2") (pinfunction "K_2") (pintype "passive"))
      (node (ref "D259") (pin "2") (pinfunction "K_2") (pintype "passive"))
      (node (ref "D260") (pin "2") (pinfunction "K_2") (pintype "passive"))
      (node (ref "D261") (pin "2") (pinfunction "K_2") (pintype "passive"))
      (node (ref "D262") (pin "2") (pinfunction "K_2") (pintype "passive"))
      (node (ref "D263") (pin "2") (pinfunction "K_2") (pintype "passive"))
      (node (ref "D264") (pin "2") (pinfunction "K_2") (pintype "passive"))
      (node (ref "D265") (pin "2") (pinfunction "K_2") (pintype "passive"))
      (node (ref "D266") (pin "2") (pinfunction "K_2") (pintype "passive"))
      (node (ref "D267") (pin "2") (pinfunction "K_2") (pintype "passive"))
      (node (ref "D268") (pin "2") (pinfunction "K_2") (pintype "passive"))
      (node (ref "D269") (pin "2") (pinfunction "K_2") (pintype "passive"))
      (node (ref "D270") (pin "2") (pinfunction "K_2") (pintype "passive"))
    )
    (net (code "20") (name "Net-(D201-A)") (class "Default")
      (node (ref "D201") (pin "1") (pinfunction "A_1") (pintype "passive"))
      (node (ref "S201") (pin "1") (pinfunction "1_1") (pintype "passive"))
    )
    (net (code "21") (name "Net-(D202-A)") (class "Default")
      (node (ref "D202") (pin "1") (pinfunction "A_1") (pintype "passive"))
      (node (ref "S202") (pin "1") (pinfunction "1_1") (pintype "passive"))
    )
    (net (code "22") (name "Net-(D203-A)") (class "Default")
      (node (ref "D203") (pin "1") (pinfunction "A_1") (pintype "passive"))
      (node (ref "S203") (pin "1") (pinfunction "1_1") (pintype "passive"))
    )
    (net (code "23") (name "Net-(D204-A)") (class "Default")
      (node (ref "D204") (pin "1") (pinfunction "A_1") (pintype "passive"))
      (node (ref "S204") (pin "1") (pinfunction "1_1") (pintype "passive"))
    )
    (net (code "24") (name "Net-(D205-A)") (class "Default")
      (node (ref "D205") (pin "1") (pinfunction "A_1") (pintype "passive"))
      (node (ref "S205") (pin "1") (pinfunction "1_1") (pintype "passive"))
    )
    (net (code "25") (name "Net-(D206-A)") (class "Default")
      (node (ref "D206") (pin "1") (pinfunction "A_1") (pintype "passive"))
      (node (ref "S206") (pin "1") (pinfunction "1_1") (pintype "passive"))
    )
    (net (code "26") (name "Net-(D207-A)") (class "Default")
      (node (ref "D207") (pin "1") (pinfunction "A_1") (pintype "passive"))
      (node (ref "S207") (pin "1") (pinfunction "1_1") (pintype "passive"))
    )
    (net (code "27") (name "Net-(D208-A)") (class "Default")
      (node (ref "D208") (pin "1") (pinfunction "A_1") (pintype "passive"))
      (node (ref "S208") (pin "1") (pinfunction "1_1") (pintype "passive"))
    )
    (net (code "28") (name "Net-(D209-A)") (class "Default")
      (node (ref "D209") (pin "1") (pinfunction "A_1") (pintype "passive"))
      (node (ref "S209") (pin "1") (pinfunction "1_1") (pintype "passive"))
    )
    (net (code "29") (name "Net-(D210-A)") (class "Default")
      (node (ref "D210") (pin "1") (pinfunction "A_1") (pintype "passive"))
      (node (ref "S210") (pin "1") (pinfunction "1_1") (pintype "passive"))
    )
    (net (code "30") (name "Net-(D211-A)") (class "Default")
      (node (ref "D211") (pin "1") (pinfunction "A_1") (pintype "passive"))
      (node (ref "S211") (pin "1") (pinfunction "1_1") (pintype "passive"))
    )
    (net (code "31") (name "Net-(D212-A)") (class "Default")
      (node (ref "D212") (pin "1") (pinfunction "A_1") (pintype "passive"))
      (node (ref "S212") (pin "1") (pinfunction "1_1") (pintype "passive"))
    )
    (net (code "32") (name "Net-(D213-A)") (class "Default")
      (node (ref "D213") (pin "1") (pinfunction "A_1") (pintype "passive"))
      (node (ref "S213") (pin "1") (pinfunction "1_1") (pintype "passive"))
    )
    (net (code "33") (name "Net-(D214-A)") (class "Default")
      (node (ref "D214") (pin "1") (pinfunction "A_1") (pintype "passive"))
      (node (ref "S214") (pin "1") (pinfunction "1_1") (pintype "passive"))
    )
    (net (code "34") (name "Net-(D215-A)") (class "Default")
      (node (ref "D215") (pin "1") (pinfunction "A_1") (pintype "passive"))
      (node (ref "S215") (pin "2") (pinfunction "2_2") (pintype "passive"))
    )
    (net (code "35") (name "Net-(D216-A)") (class "Default")
      (node (ref "D216") (pin "1") (pinfunction "A_1") (pintype "passive"))
      (node (ref "S216") (pin "1") (pinfunction "1_1") (pintype "passive"))
    )
    (net (code "36") (name "Net-(D217-A)") (class "Default")
      (node (ref "D217") (pin "1") (pinfunction "A_1") (pintype "passive"))
      (node (ref "S217") (pin "1") (pinfunction "1_1") (pintype "passive"))
    )
    (net (code "37") (name "Net-(D218-A)") (class "Default")
      (node (ref "D218") (pin "1") (pinfunction "A_1") (pintype "passive"))
      (node (ref "S218") (pin "1") (pinfunction "1_1") (pintype "passive"))
    )
    (net (code "38") (name "Net-(D219-A)") (class "Default")
      (node (ref "D219") (pin "1") (pinfunction "A_1") (pintype "passive"))
      (node (ref "S219") (pin "1") (pinfunction "1_1") (pintype "passive"))
    )
    (net (code "39") (name "Net-(D220-A)") (class "Default")
      (node (ref "D220") (pin "1") (pinfunction "A_1") (pintype "passive"))
      (node (ref "S220") (pin "1") (pinfunction "1_1") (pintype "passive"))
    )
    (net (code "40") (name "Net-(D221-A)") (class "Default")
      (node (ref "D221") (pin "1") (pinfunction "A_1") (pintype "passive"))
      (node (ref "S221") (pin "1") (pinfunction "1_1") (pintype "passive"))
    )
    (net (code "41") (name "Net-(D222-A)") (class "Default")
      (node (ref "D222") (pin "1") (pinfunction "A_1") (pintype "passive"))
      (node (ref "S222") (pin "1") (pinfunction "1_1") (pintype "passive"))
    )
    (net (code "42") (name "Net-(D223-A)") (class "Default")
      (node (ref "D223") (pin "1") (pinfunction "A_1") (pintype "passive"))
      (node (ref "S223") (pin "1") (pinfunction "1_1") (pintype "passive"))
    )
    (net (code "43") (name "Net-(D224-A)") (class "Default")
      (node (ref "D224") (pin "1") (pinfunction "A_1") (pintype "passive"))
      (node (ref "S224") (pin "1") (pinfunction "1_1") (pintype "passive"))
    )
    (net (code "44") (name "Net-(D225-A)") (class "Default")
      (node (ref "D225") (pin "1") (pinfunction "A_1") (pintype "passive"))
      (node (ref "S225") (pin "1") (pinfunction "1_1") (pintype "passive"))
    )
    (net (code "45") (name "Net-(D226-A)") (class "Default")
      (node (ref "D226") (pin "1") (pinfunction "A_1") (pintype "passive"))
      (node (ref "S226") (pin "1") (pinfunction "1_1") (pintype "passive"))
    )
    (net (code "46") (name "Net-(D227-A)") (class "Default")
      (node (ref "D227") (pin "1") (pinfunction "A_1") (pintype "passive"))
      (node (ref "S227") (pin "1") (pinfunction "1_1") (pintype "passive"))
    )
    (net (code "47") (name "Net-(D228-A)") (class "Default")
      (node (ref "D228") (pin "1") (pinfunction "A_1") (pintype "passive"))
      (node (ref "S228") (pin "1") (pinfunction "1_1") (pintype "passive"))
    )
    (net (code "48") (name "Net-(D229-A)") (class "Default")
      (node (ref "D229") (pin "1") (pinfunction "A_1") (pintype "passive"))
      (node (ref "S229") (pin "1") (pinfunction "1_1") (pintype "passive"))
    )
    (net (code "49") (name "Net-(D230-A)") (class "Default")
      (node (ref "D230") (pin "1") (pinfunction "A_1") (pintype "passive"))
      (node (ref "S230") (pin "1") (pinfunction "1_1") (pintype "passive"))
    )
    (net (code "50") (name "Net-(D231-A)") (class "Default")
      (node (ref "D231") (pin "1") (pinfunction "A_1") (pintype "passive"))
      (node (ref "S231") (pin "1") (pinfunction "1_1") (pintype "passive"))
    )
    (net (code "51") (name "Net-(D232-A)") (class "Default")
      (node (ref "D232") (pin "1") (pinfunction "A_1") (pintype "passive"))
      (node (ref "S232") (pin "1") (pinfunction "1_1") (pintype "passive"))
    )
    (net (code "52") (name "Net-(D233-A)") (class "Default")
      (node (ref "D233") (pin "1") (pinfunction "A_1") (pintype "passive"))
      (node (ref "S233") (pin "1") (pinfunction "1_1") (pintype "passive"))
    )
    (net (code "53") (name "Net-(D234-A)") (class "Default")
      (node (ref "D234") (pin "1") (pinfunction "A_1") (pintype "passive"))
      (node (ref "S234") (pin "1") (pinfunction "1_1") (pintype "passive"))
    )
    (net (code "54") (name "Net-(D235-A)") (class "Default")
      (node (ref "D235") (pin "1") (pinfunction "A_1") (pintype "passive"))
      (node (ref "S235") (pin "1") (pinfunction "1_1") (pintype "passive"))
    )
    (net (code "55") (name "Net-(D236-A)") (class "Default")
      (node (ref "D236") (pin "1") (pinfunction "A_1") (pintype "passive"))
      (node (ref "S236") (pin "1") (pinfunction "1_1") (pintype "passive"))
    )
    (net (code "56") (name "Net-(D237-A)") (class "Default")
      (node (ref "D237") (pin "1") (pinfunction "A_1") (pintype "passive"))
      (node (ref "S237") (pin "1") (pinfunction "1_1") (pintype "passive"))
    )
    (net (code "57") (name "Net-(D238-A)") (class "Default")
      (node (ref "D238") (pin "1") (pinfunction "A_1") (pintype "passive"))
      (node (ref "S238") (pin "1") (pinfunction "1_1") (pintype "passive"))
    )
    (net (code "58") (name "Net-(D239-A)") (class "Default")
      (node (ref "D239") (pin "1") (pinfunction "A_1") (pintype "passive"))
      (node (ref "S239") (pin "1") (pinfunction "1_1") (pintype "passive"))
    )
    (net (code "59") (name "Net-(D240-A)") (class "Default")
      (node (ref "D240") (pin "1") (pinfunction "A_1") (pintype "passive"))
      (node (ref "S240") (pin "1") (pinfunction "1_1") (pintype "passive"))
    )
    (net (code "60") (name "Net-(D241-A)") (class "Default")
      (node (ref "D241") (pin "1") (pinfunction "A_1") (pintype "passive"))
      (node (ref "S241") (pin "1") (pinfunction "1_1") (pintype "passive"))
    )
    (net (code "61") (name "Net-(D242-A)") (class "Default")
      (node (ref "D242") (pin "1") (pinfunction "A_1") (pintype "passive"))
      (node (ref "S242") (pin "1") (pinfunction "1_1") (pintype "passive"))
    )
    (net (code "62") (name "Net-(D243-A)") (class "Default")
      (node (ref "D243") (pin "1") (pinfunction "A_1") (pintype "passive"))
      (node (ref "S243") (pin "1") (pinfunction "1_1") (pintype "passive"))
    )
    (net (code "63") (name "Net-(D244-A)") (class "Default")
      (node (ref "D244") (pin "1") (pinfunction "A_1") (pintype "passive"))
      (node (ref "S244") (pin "1") (pinfunction "1_1") (pintype "passive"))
    )
    (net (code "64") (name "Net-(D245-A)") (class "Default")
      (node (ref "D245") (pin "1") (pinfunction "A_1") (pintype "passive"))
      (node (ref "S245") (pin "1") (pinfunction "1_1") (pintype "passive"))
    )
    (net (code "65") (name "Net-(D246-A)") (class "Default")
      (node (ref "D246") (pin "1") (pinfunction "A_1") (pintype "passive"))
      (node (ref "S246") (pin "1") (pinfunction "1_1") (pintype "passive"))
    )
    (net (code "66") (name "Net-(D247-A)") (class "Default")
      (node (ref "D247") (pin "1") (pinfunction "A_1") (pintype "passive"))
      (node (ref "S247") (pin "1") (pinfunction "1_1") (pintype "passive"))
    )
    (net (code "67") (name "Net-(D248-A)") (class "Default")
      (node (ref "D248") (pin "1") (pinfunction "A_1") (pintype "passive"))
      (node (ref "S248") (pin "1") (pinfunction "1_1") (pintype "passive"))
    )
    (net (code "68") (name "Net-(D249-A)") (class "Default")
      (node (ref "D249") (pin "1") (pinfunction "A_1") (pintype "passive"))
      (node (ref "S249") (pin "1") (pinfunction "1_1") (pintype "passive"))
    )
    (net (code "69") (name "Net-(D250-A)") (class "Default")
      (node (ref "D250") (pin "1") (pinfunction "A_1") (pintype "passive"))
      (node (ref "S250") (pin "1") (pinfunction "1_1") (pintype "passive"))
    )
    (net (code "70") (name "Net-(D251-A)") (class "Default")
      (node (ref "D251") (pin "1") (pinfunction "A_1") (pintype "passive"))
      (node (ref "S251") (pin "1") (pinfunction "1_1") (pintype "passive"))
    )
    (net (code "71") (name "Net-(D252-A)") (class "Default")
      (node (ref "D252") (pin "1") (pinfunction "A_1") (pintype "passive"))
      (node (ref "S252") (pin "1") (pinfunction "1_1") (pintype "passive"))
    )
    (net (code "72") (name "Net-(D253-A)") (class "Default")
      (node (ref "D253") (pin "1") (pinfunction "A_1") (pintype "passive"))
      (node (ref "S253") (pin "1") (pinfunction "1_1") (pintype "passive"))
    )
    (net (code "73") (name "Net-(D254-A)") (class "Default")
      (node (ref "D254") (pin "1") (pinfunction "A_1") (pintype "passive"))
      (node (ref "S254") (pin "1") (pinfunction "1_1") (pintype "passive"))
    )
    (net (code "74") (name "Net-(D255-A)") (class "Default")
      (node (ref "D255") (pin "1") (pinfunction "A_1") (pintype "passive"))
      (node (ref "S255") (pin "1") (pinfunction "1_1") (pintype "passive"))
    )
    (net (code "75") (name "Net-(D256-A)") (class "Default")
      (node (ref "D256") (pin "1") (pinfunction "A_1") (pintype "passive"))
      (node (ref "S256") (pin "1") (pinfunction "1_1") (pintype "passive"))
    )
    (net (code "76") (name "Net-(D257-A)") (class "Default")
      (node (ref "D257") (pin "1") (pinfunction "A_1") (pintype "passive"))
      (node (ref "S257") (pin "1") (pinfunction "1_1") (pintype "passive"))
    )
    (net (code "77") (name "Net-(D258-A)") (class "Default")
      (node (ref "D258") (pin "1") (pinfunction "A_1") (pintype "passive"))
      (node (ref "S258") (pin "1") (pinfunction "1_1") (pintype "passive"))
    )
    (net (code "78") (name "Net-(D259-A)") (class "Default")
      (node (ref "D259") (pin "1") (pinfunction "A_1") (pintype "passive"))
      (node (ref "S259") (pin "1") (pinfunction "1_1") (pintype "passive"))
    )
    (net (code "79") (name "Net-(D260-A)") (class "Default")
      (node (ref "D260") (pin "1") (pinfunction "A_1") (pintype "passive"))
      (node (ref "S260") (pin "1") (pinfunction "1_1") (pintype "passive"))
    )
    (net (code "80") (name "Net-(D261-A)") (class "Default")
      (node (ref "D261") (pin "1") (pinfunction "A_1") (pintype "passive"))
      (node (ref "S261") (pin "1") (pinfunction "1_1") (pintype "passive"))
    )
    (net (code "81") (name "Net-(D262-A)") (class "Default")
      (node (ref "D262") (pin "1") (pinfunction "A_1") (pintype "passive"))
      (node (ref "S262") (pin "1") (pinfunction "1_1") (pintype "passive"))
    )
    (net (code "82") (name "Net-(D263-A)") (class "Default")
      (node (ref "D263") (pin "1") (pinfunction "A_1") (pintype "passive"))
      (node (ref "S263") (pin "1") (pinfunction "1_1") (pintype "passive"))
    )
    (net (code "83") (name "Net-(D264-A)") (class "Default")
      (node (ref "D264") (pin "1") (pinfunction "A_1") (pintype "passive"))
      (node (ref "S264") (pin "1") (pinfunction "1_1") (pintype "passive"))
    )
    (net (code "84") (name "Net-(D265-A)") (class "Default")
      (node (ref "D265") (pin "1") (pinfunction "A_1") (pintype "passive"))
      (node (ref "S265") (pin "1") (pinfunction "1_1") (pintype "passive"))
    )
    (net (code "85") (name "Net-(D266-A)") (class "Default")
      (node (ref "D266") (pin "1") (pinfunction "A_1") (pintype "passive"))
      (node (ref "S266") (pin "1") (pinfunction "1_1") (pintype "passive"))
    )
    (net (code "86") (name "Net-(D267-A)") (class "Default")
      (node (ref "D267") (pin "1") (pinfunction "A_1") (pintype "passive"))
      (node (ref "S267") (pin "1") (pinfunction "1_1") (pintype "passive"))
    )
    (net (code "87") (name "Net-(D268-A)") (class "Default")
      (node (ref "D268") (pin "1") (pinfunction "A_1") (pintype "passive"))
      (node (ref "S268") (pin "1") (pinfunction "1_1") (pintype "passive"))
    )
    (net (code "88") (name "Net-(D269-A)") (class "Default")
      (node (ref "D269") (pin "1") (pinfunction "A_1") (pintype "passive"))
      (node (ref "S269") (pin "1") (pinfunction "1_1") (pintype "passive"))
    )
    (net (code "89") (name "Net-(D270-A)") (class "Default")
      (node (ref "D270") (pin "1") (pinfunction "A_1") (pintype "passive"))
      (node (ref "S270") (pin "1") (pinfunction "1_1") (pintype "passive"))
    )
  )
)
